# DS1307.net
KiCad netlist of a schematic drawn in EAGLE
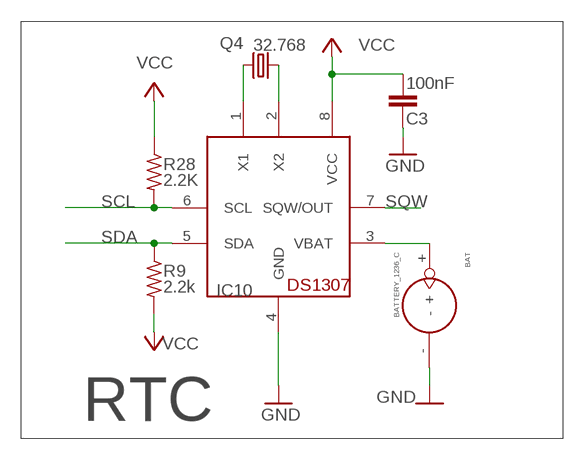
[diagram p0: schematic, sheet 1]

(export (version "E")
  (design (tool "Eeschema 10.0.6"))
  (components
    (comp (ref "BAT")
      (value "BATTERY_1236_C")
      (footprint "eagle-import:BATTERY_1236_C")
      (libsource (lib "eagle-import") (part "BATTERY_1236_C"))
    )
    (comp (ref "C3")
      (value "100nF")
      (footprint "eagle-import:C050-024X044")
      (libsource (lib "eagle-import") (part "C-EU050-024X044"))
    )
    (comp (ref "IC10")
      (value "DS1307")
      (footprint "eagle-import:DIL08")
      (libsource (lib "eagle-import") (part "DS1307"))
    )
    (comp (ref "Q4")
      (value "32.768")
      (footprint "eagle-import:TC38H")
      (libsource (lib "eagle-import") (part "CRYTALTC38H"))
    )
    (comp (ref "R9")
      (value "2.2k")
      (footprint "eagle-import:0204_7")
      (libsource (lib "eagle-import") (part "R-US_0204/7"))
    )
    (comp (ref "R28")
      (value "2.2K")
      (footprint "eagle-import:0204_7")
      (libsource (lib "eagle-import") (part "R-US_0204/7"))
    )
  )
  (nets
    (net (code "1") (name "/SCL") (class "Default")
      (node (ref "IC10") (pin "6") (pinfunction "SCL_6") (pintype "bidirectional"))
      (node (ref "R28") (pin "2") (pinfunction "2_2") (pintype "passive"))
    )
    (net (code "2") (name "/SDA") (class "Default")
      (node (ref "IC10") (pin "5") (pinfunction "SDA_5") (pintype "bidirectional"))
      (node (ref "R9") (pin "1") (pinfunction "1_1") (pintype "passive"))
    )
    (net (code "3") (name "/SQW") (class "Default")
      (node (ref "IC10") (pin "7") (pinfunction "SQW/OUT_7") (pintype "bidirectional"))
    )
    (net (code "4") (name "GND") (class "Default")
      (node (ref "BAT") (pin "-") (pinfunction "-_-") (pintype "bidirectional"))
      (node (ref "C3") (pin "1") (pinfunction "1_1") (pintype "passive"))
      (node (ref "IC10") (pin "4") (pinfunction "GND_4") (pintype "power_in"))
    )
    (net (code "5") (name "Net-(IC10-VBAT)") (class "Default")
      (node (ref "BAT") (pin "+") (pinfunction "+_+") (pintype "bidirectional"))
      (node (ref "IC10") (pin "3") (pinfunction "VBAT_3") (pintype "power_in"))
    )
    (net (code "6") (name "Net-(IC10-X1)") (class "Default")
      (node (ref "IC10") (pin "1") (pinfunction "X1_1") (pintype "passive"))
      (node (ref "Q4") (pin "2") (pinfunction "2_2") (pintype "passive"))
    )
    (net (code "7") (name "Net-(IC10-X2)") (class "Default")
      (node (ref "IC10") (pin "2") (pinfunction "X2_2") (pintype "passive"))
      (node (ref "Q4") (pin "1") (pinfunction "1_1") (pintype "passive"))
    )
    (net (code "8") (name "VCC") (class "Default")
      (node (ref "C3") (pin "2") (pinfunction "2_2") (pintype "passive"))
      (node (ref "IC10") (pin "8") (pinfunction "VCC_8") (pintype "power_in"))
      (node (ref "R28") (pin "1") (pinfunction "1_1") (pintype "passive"))
      (node (ref "R9") (pin "2") (pinfunction "2_2") (pintype "passive"))
    )
  )
)
